# AIRDC.net
KiCad netlist of a schematic drawn in EAGLE
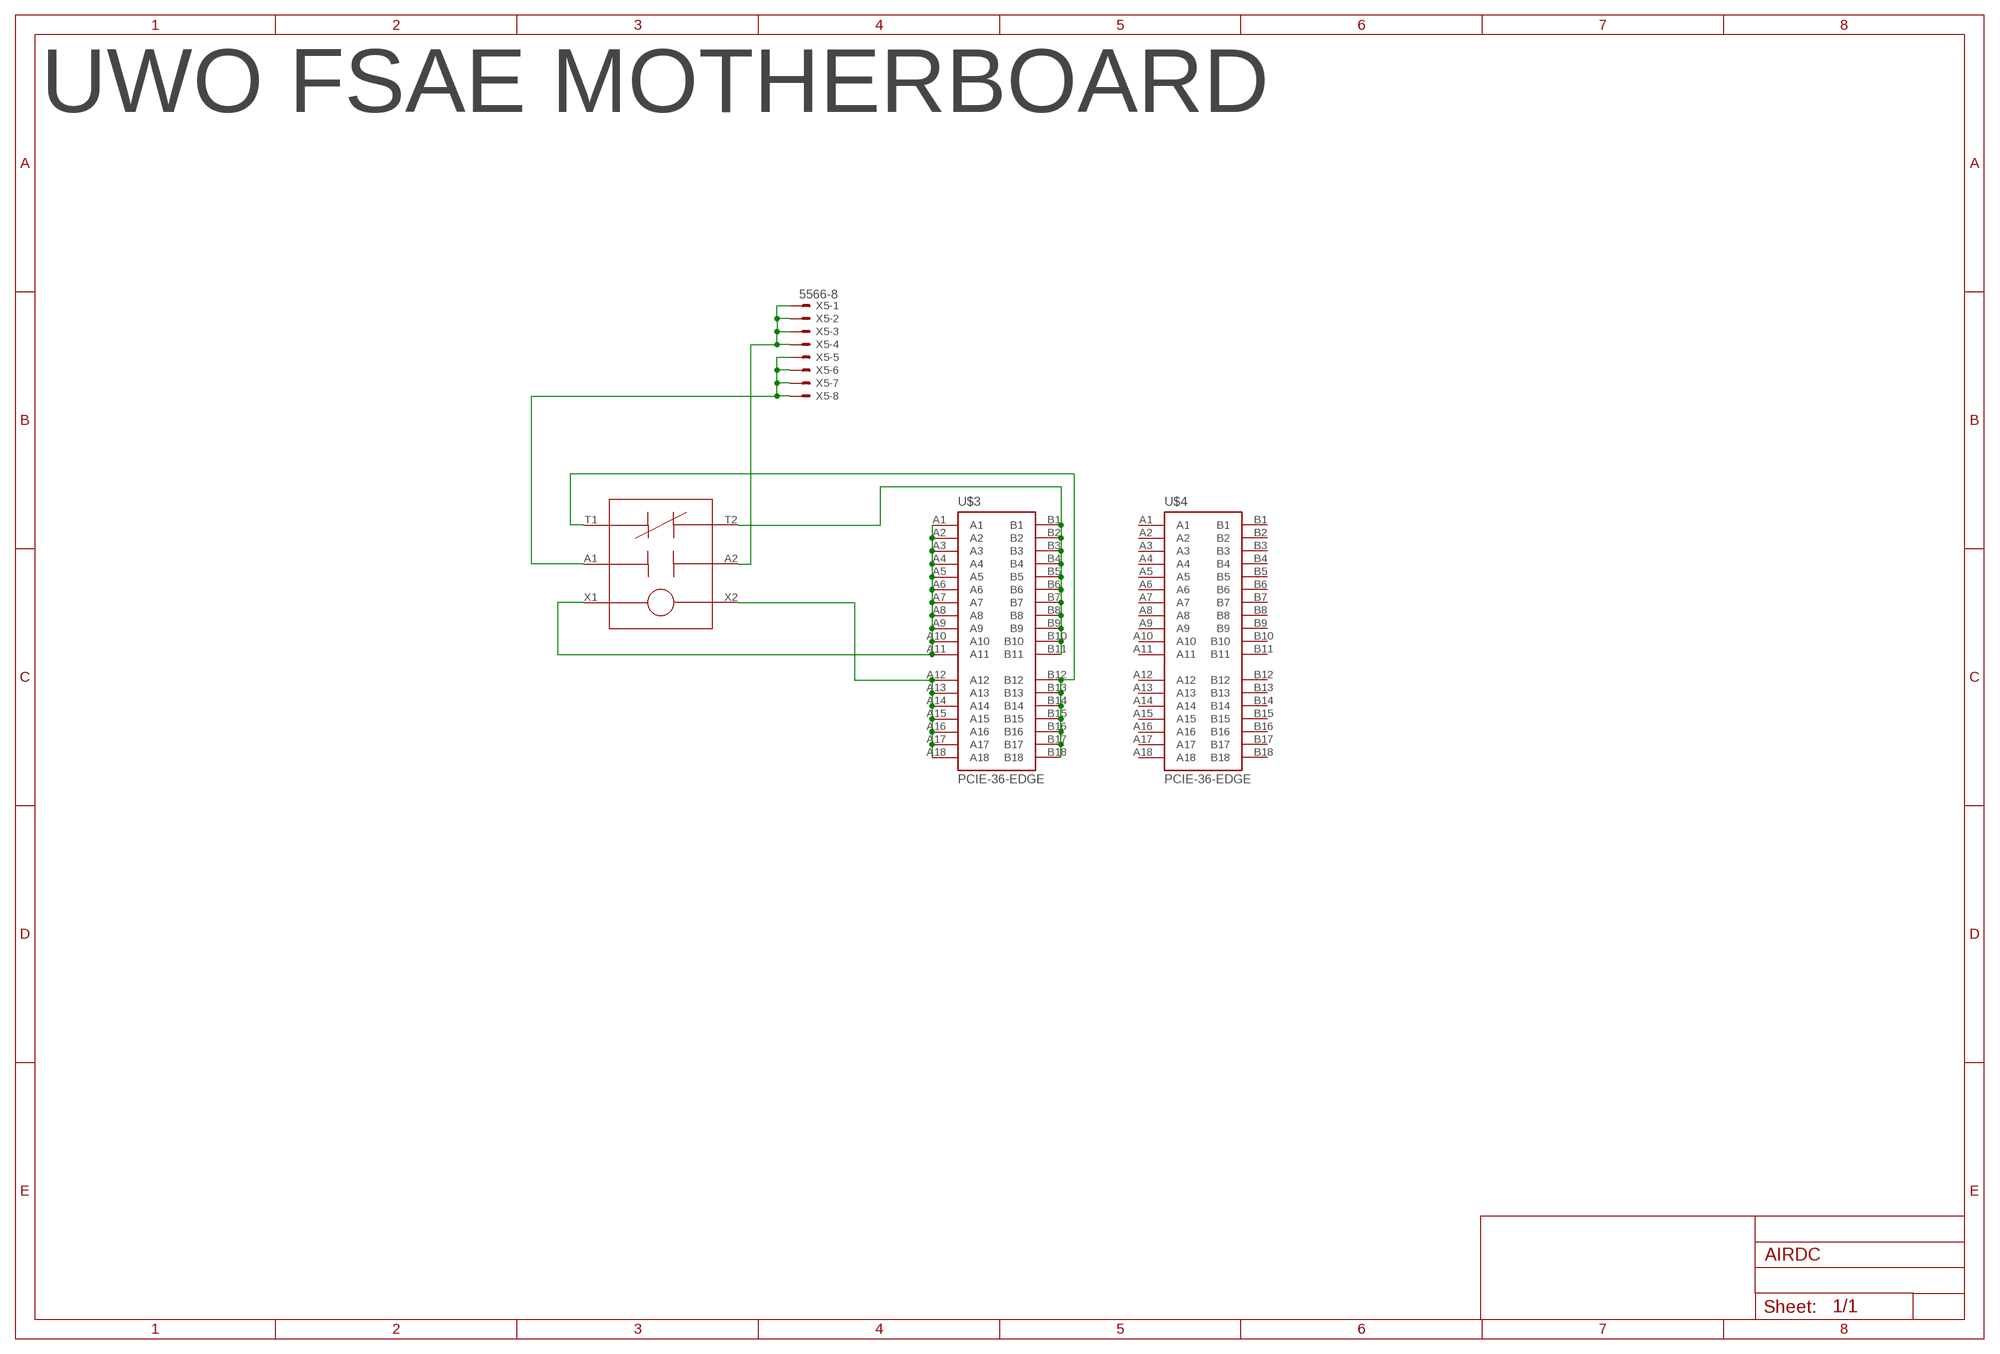
[diagram p0: schematic, sheet 1]

(export (version "E")
  (design (tool "Eeschema 10.0.6"))
  (components
    (comp (ref "U$1")
      (value "GV224")
      (footprint "eagle-import:GV224")
      (libsource (lib "eagle-import") (part "GV224"))
    )
    (comp (ref "U$3")
      (value "PCIE-36-EDGE")
      (footprint "eagle-import:PCI-E_SLOT_36")
      (libsource (lib "eagle-import") (part "PCIE-36-EDGE"))
    )
    (comp (ref "U$4")
      (value "PCIE-36-EDGE")
      (footprint "eagle-import:PCI-E_SLOT_36")
      (libsource (lib "eagle-import") (part "PCIE-36-EDGE"))
    )
    (comp (ref "X5")
      (value "5566-8")
      (footprint "eagle-import:5566-8")
      (fields (field (name "MF") "MOLEX"))
      (libsource (lib "eagle-import") (part "5566-8"))
    )
  )
  (nets
    (net (code "1") (name "Net-(U$1-PadT1)") (class "Default")
      (node (ref "U$1") (pin "T1") (pinfunction "T1_T1") (pintype "bidirectional"))
      (node (ref "U$3") (pin "B12") (pinfunction "B12_B12") (pintype "passive"))
      (node (ref "U$3") (pin "B13") (pinfunction "B13_B13") (pintype "passive"))
      (node (ref "U$3") (pin "B14") (pinfunction "B14_B14") (pintype "passive"))
      (node (ref "U$3") (pin "B15") (pinfunction "B15_B15") (pintype "passive"))
      (node (ref "U$3") (pin "B16") (pinfunction "B16_B16") (pintype "passive"))
      (node (ref "U$3") (pin "B17") (pinfunction "B17_B17") (pintype "passive"))
      (node (ref "U$3") (pin "B18") (pinfunction "B18_B18") (pintype "passive"))
    )
    (net (code "2") (name "Net-(U$1-PadT2)") (class "Default")
      (node (ref "U$1") (pin "T2") (pinfunction "T2_T2") (pintype "bidirectional"))
      (node (ref "U$3") (pin "B1") (pinfunction "B1_B1") (pintype "passive"))
      (node (ref "U$3") (pin "B10") (pinfunction "B10_B10") (pintype "passive"))
      (node (ref "U$3") (pin "B11") (pinfunction "B11_B11") (pintype "passive"))
      (node (ref "U$3") (pin "B2") (pinfunction "B2_B2") (pintype "passive"))
      (node (ref "U$3") (pin "B3") (pinfunction "B3_B3") (pintype "passive"))
      (node (ref "U$3") (pin "B4") (pinfunction "B4_B4") (pintype "passive"))
      (node (ref "U$3") (pin "B5") (pinfunction "B5_B5") (pintype "passive"))
      (node (ref "U$3") (pin "B6") (pinfunction "B6_B6") (pintype "passive"))
      (node (ref "U$3") (pin "B7") (pinfunction "B7_B7") (pintype "passive"))
      (node (ref "U$3") (pin "B8") (pinfunction "B8_B8") (pintype "passive"))
      (node (ref "U$3") (pin "B9") (pinfunction "B9_B9") (pintype "passive"))
    )
    (net (code "3") (name "Net-(U$1-PadX1)") (class "Default")
      (node (ref "U$1") (pin "X1") (pinfunction "X1_X1") (pintype "bidirectional"))
      (node (ref "U$3") (pin "A1") (pinfunction "A1_A1") (pintype "passive"))
      (node (ref "U$3") (pin "A10") (pinfunction "A10_A10") (pintype "passive"))
      (node (ref "U$3") (pin "A11") (pinfunction "A11_A11") (pintype "passive"))
      (node (ref "U$3") (pin "A2") (pinfunction "A2_A2") (pintype "passive"))
      (node (ref "U$3") (pin "A3") (pinfunction "A3_A3") (pintype "passive"))
      (node (ref "U$3") (pin "A4") (pinfunction "A4_A4") (pintype "passive"))
      (node (ref "U$3") (pin "A5") (pinfunction "A5_A5") (pintype "passive"))
      (node (ref "U$3") (pin "A6") (pinfunction "A6_A6") (pintype "passive"))
      (node (ref "U$3") (pin "A7") (pinfunction "A7_A7") (pintype "passive"))
      (node (ref "U$3") (pin "A8") (pinfunction "A8_A8") (pintype "passive"))
      (node (ref "U$3") (pin "A9") (pinfunction "A9_A9") (pintype "passive"))
    )
    (net (code "4") (name "Net-(U$1-PadX2)") (class "Default")
      (node (ref "U$1") (pin "X2") (pinfunction "X2_X2") (pintype "bidirectional"))
      (node (ref "U$3") (pin "A12") (pinfunction "A12_A12") (pintype "passive"))
      (node (ref "U$3") (pin "A13") (pinfunction "A13_A13") (pintype "passive"))
      (node (ref "U$3") (pin "A14") (pinfunction "A14_A14") (pintype "passive"))
      (node (ref "U$3") (pin "A15") (pinfunction "A15_A15") (pintype "passive"))
      (node (ref "U$3") (pin "A16") (pinfunction "A16_A16") (pintype "passive"))
      (node (ref "U$3") (pin "A17") (pinfunction "A17_A17") (pintype "passive"))
      (node (ref "U$3") (pin "A18") (pinfunction "A18_A18") (pintype "passive"))
    )
    (net (code "5") (name "Net-(X5A-S)") (class "Default")
      (node (ref "U$1") (pin "A2") (pinfunction "A2_A2") (pintype "bidirectional"))
      (node (ref "X5") (pin "1") (pinfunction "S_1") (pintype "passive"))
      (node (ref "X5") (pin "2") (pinfunction "S_2") (pintype "passive"))
      (node (ref "X5") (pin "3") (pinfunction "S_3") (pintype "passive"))
      (node (ref "X5") (pin "4") (pinfunction "S_4") (pintype "passive"))
    )
    (net (code "6") (name "Net-(X5E-S)") (class "Default")
      (node (ref "U$1") (pin "A1") (pinfunction "A1_A1") (pintype "bidirectional"))
      (node (ref "X5") (pin "5") (pinfunction "S_5") (pintype "passive"))
      (node (ref "X5") (pin "6") (pinfunction "S_6") (pintype "passive"))
      (node (ref "X5") (pin "7") (pinfunction "S_7") (pintype "passive"))
      (node (ref "X5") (pin "8") (pinfunction "S_8") (pintype "passive"))
    )
    (net (code "7") (name "unconnected-(U$4-PadA1)") (class "Default")
      (node (ref "U$4") (pin "A1") (pinfunction "A1_A1") (pintype "passive"))
    )
    (net (code "8") (name "unconnected-(U$4-PadA2)") (class "Default")
      (node (ref "U$4") (pin "A2") (pinfunction "A2_A2") (pintype "passive"))
    )
    (net (code "9") (name "unconnected-(U$4-PadA3)") (class "Default")
      (node (ref "U$4") (pin "A3") (pinfunction "A3_A3") (pintype "passive"))
    )
    (net (code "10") (name "unconnected-(U$4-PadA4)") (class "Default")
      (node (ref "U$4") (pin "A4") (pinfunction "A4_A4") (pintype "passive"))
    )
    (net (code "11") (name "unconnected-(U$4-PadA5)") (class "Default")
      (node (ref "U$4") (pin "A5") (pinfunction "A5_A5") (pintype "passive"))
    )
    (net (code "12") (name "unconnected-(U$4-PadA6)") (class "Default")
      (node (ref "U$4") (pin "A6") (pinfunction "A6_A6") (pintype "passive"))
    )
    (net (code "13") (name "unconnected-(U$4-PadA7)") (class "Default")
      (node (ref "U$4") (pin "A7") (pinfunction "A7_A7") (pintype "passive"))
    )
    (net (code "14") (name "unconnected-(U$4-PadA8)") (class "Default")
      (node (ref "U$4") (pin "A8") (pinfunction "A8_A8") (pintype "passive"))
    )
    (net (code "15") (name "unconnected-(U$4-PadA9)") (class "Default")
      (node (ref "U$4") (pin "A9") (pinfunction "A9_A9") (pintype "passive"))
    )
    (net (code "16") (name "unconnected-(U$4-PadA10)") (class "Default")
      (node (ref "U$4") (pin "A10") (pinfunction "A10_A10") (pintype "passive"))
    )
    (net (code "17") (name "unconnected-(U$4-PadA11)") (class "Default")
      (node (ref "U$4") (pin "A11") (pinfunction "A11_A11") (pintype "passive"))
    )
    (net (code "18") (name "unconnected-(U$4-PadA12)") (class "Default")
      (node (ref "U$4") (pin "A12") (pinfunction "A12_A12") (pintype "passive"))
    )
    (net (code "19") (name "unconnected-(U$4-PadA13)") (class "Default")
      (node (ref "U$4") (pin "A13") (pinfunction "A13_A13") (pintype "passive"))
    )
    (net (code "20") (name "unconnected-(U$4-PadA14)") (class "Default")
      (node (ref "U$4") (pin "A14") (pinfunction "A14_A14") (pintype "passive"))
    )
    (net (code "21") (name "unconnected-(U$4-PadA15)") (class "Default")
      (node (ref "U$4") (pin "A15") (pinfunction "A15_A15") (pintype "passive"))
    )
    (net (code "22") (name "unconnected-(U$4-PadA16)") (class "Default")
      (node (ref "U$4") (pin "A16") (pinfunction "A16_A16") (pintype "passive"))
    )
    (net (code "23") (name "unconnected-(U$4-PadA17)") (class "Default")
      (node (ref "U$4") (pin "A17") (pinfunction "A17_A17") (pintype "passive"))
    )
    (net (code "24") (name "unconnected-(U$4-PadA18)") (class "Default")
      (node (ref "U$4") (pin "A18") (pinfunction "A18_A18") (pintype "passive"))
    )
    (net (code "25") (name "unconnected-(U$4-PadB1)") (class "Default")
      (node (ref "U$4") (pin "B1") (pinfunction "B1_B1") (pintype "passive"))
    )
    (net (code "26") (name "unconnected-(U$4-PadB2)") (class "Default")
      (node (ref "U$4") (pin "B2") (pinfunction "B2_B2") (pintype "passive"))
    )
    (net (code "27") (name "unconnected-(U$4-PadB3)") (class "Default")
      (node (ref "U$4") (pin "B3") (pinfunction "B3_B3") (pintype "passive"))
    )
    (net (code "28") (name "unconnected-(U$4-PadB4)") (class "Default")
      (node (ref "U$4") (pin "B4") (pinfunction "B4_B4") (pintype "passive"))
    )
    (net (code "29") (name "unconnected-(U$4-PadB5)") (class "Default")
      (node (ref "U$4") (pin "B5") (pinfunction "B5_B5") (pintype "passive"))
    )
    (net (code "30") (name "unconnected-(U$4-PadB6)") (class "Default")
      (node (ref "U$4") (pin "B6") (pinfunction "B6_B6") (pintype "passive"))
    )
    (net (code "31") (name "unconnected-(U$4-PadB7)") (class "Default")
      (node (ref "U$4") (pin "B7") (pinfunction "B7_B7") (pintype "passive"))
    )
    (net (code "32") (name "unconnected-(U$4-PadB8)") (class "Default")
      (node (ref "U$4") (pin "B8") (pinfunction "B8_B8") (pintype "passive"))
    )
    (net (code "33") (name "unconnected-(U$4-PadB9)") (class "Default")
      (node (ref "U$4") (pin "B9") (pinfunction "B9_B9") (pintype "passive"))
    )
    (net (code "34") (name "unconnected-(U$4-PadB10)") (class "Default")
      (node (ref "U$4") (pin "B10") (pinfunction "B10_B10") (pintype "passive"))
    )
    (net (code "35") (name "unconnected-(U$4-PadB11)") (class "Default")
      (node (ref "U$4") (pin "B11") (pinfunction "B11_B11") (pintype "passive"))
    )
    (net (code "36") (name "unconnected-(U$4-PadB12)") (class "Default")
      (node (ref "U$4") (pin "B12") (pinfunction "B12_B12") (pintype "passive"))
    )
    (net (code "37") (name "unconnected-(U$4-PadB13)") (class "Default")
      (node (ref "U$4") (pin "B13") (pinfunction "B13_B13") (pintype "passive"))
    )
    (net (code "38") (name "unconnected-(U$4-PadB14)") (class "Default")
      (node (ref "U$4") (pin "B14") (pinfunction "B14_B14") (pintype "passive"))
    )
    (net (code "39") (name "unconnected-(U$4-PadB15)") (class "Default")
      (node (ref "U$4") (pin "B15") (pinfunction "B15_B15") (pintype "passive"))
    )
    (net (code "40") (name "unconnected-(U$4-PadB16)") (class "Default")
      (node (ref "U$4") (pin "B16") (pinfunction "B16_B16") (pintype "passive"))
    )
    (net (code "41") (name "unconnected-(U$4-PadB17)") (class "Default")
      (node (ref "U$4") (pin "B17") (pinfunction "B17_B17") (pintype "passive"))
    )
    (net (code "42") (name "unconnected-(U$4-PadB18)") (class "Default")
      (node (ref "U$4") (pin "B18") (pinfunction "B18_B18") (pintype "passive"))
    )
  )
)
